# PowerClocks.net
KiCad netlist of a schematic drawn in Altium Designer
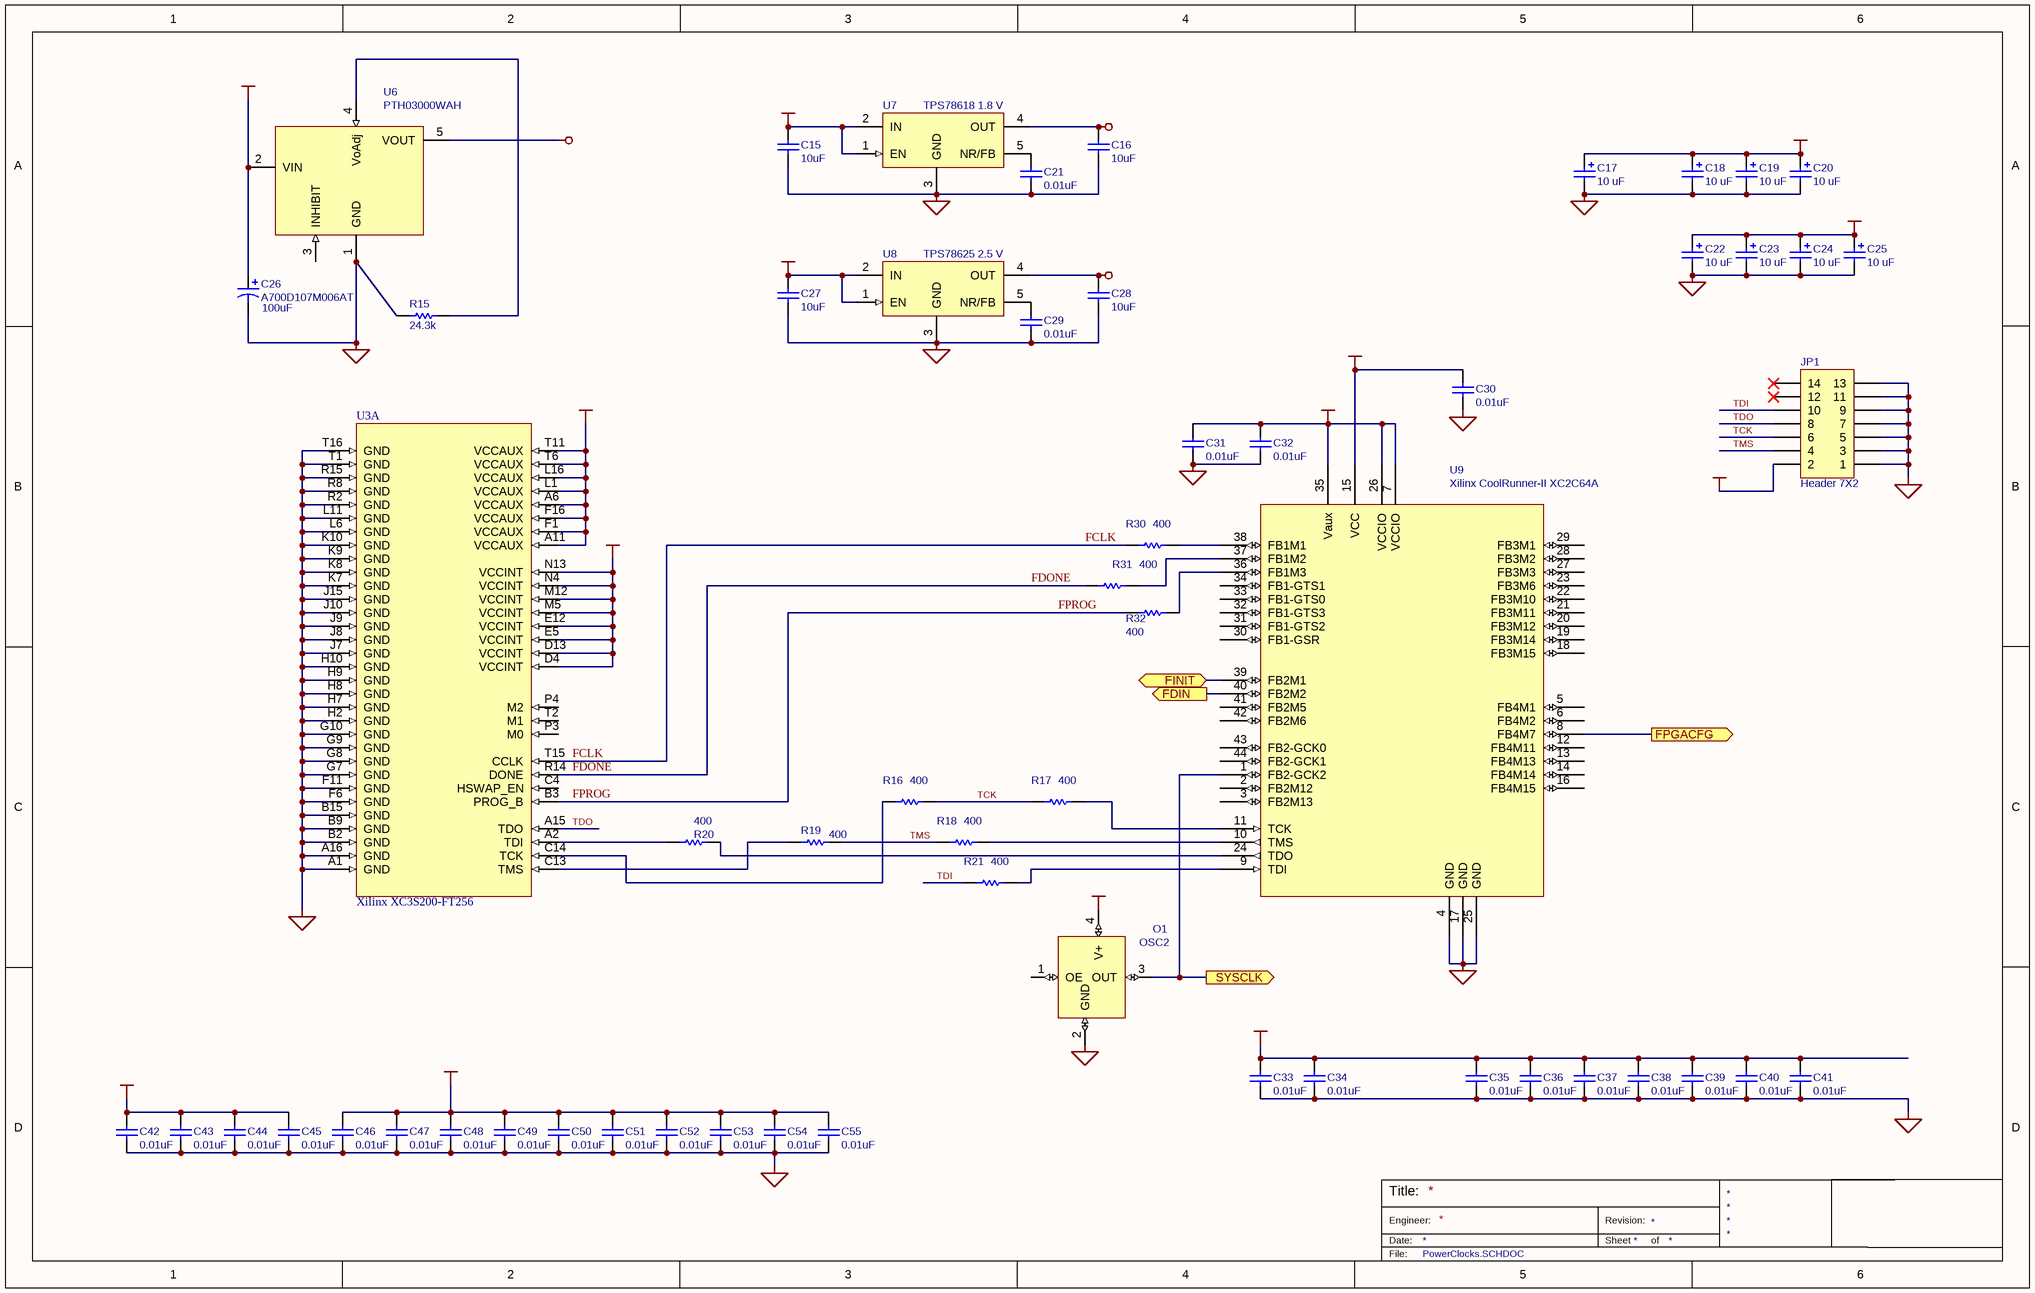
[diagram p0: PowerClocks.SCHDOC]

(export (version "E")
  (design (tool "Eeschema 10.0.6"))
  (components
    (comp (ref "C15")
      (value "10uF")
      (footprint "CC3216-1206")
      (description "Capacitor")
      (fields (field (name "PUBLISHER") "Altium Limited"))
      (libsource (lib "Miscellaneous Devices") (part "Cap"))
    )
    (comp (ref "C16")
      (value "10uF")
      (footprint "CC3216-1206")
      (description "Capacitor")
      (fields (field (name "PUBLISHER") "Altium Limited"))
      (libsource (lib "Miscellaneous Devices") (part "Cap"))
    )
    (comp (ref "C17")
      (value "10 uF")
      (footprint "TC3528-1411")
      (description "Tantalum Bypass cap")
      (fields
        (field (name "MANUFACTURER") "Generic Components")
        (field (name "Comment") "Bypass Cap")
        (field (name "PUBLISHER") "Altium Limited")
      )
      (libsource (lib "Miscellaneous Devices") (part "Cap Pol3"))
    )
    (comp (ref "C18")
      (value "10 uF")
      (footprint "TC3528-1411")
      (description "Tantalum Bypass cap")
      (fields
        (field (name "MANUFACTURER") "Generic Components")
        (field (name "Comment") "Bypass Cap")
        (field (name "PUBLISHER") "Altium Limited")
      )
      (libsource (lib "Miscellaneous Devices") (part "Cap Pol3"))
    )
    (comp (ref "C19")
      (value "10 uF")
      (footprint "TC3528-1411")
      (description "Tantalum Bypass cap")
      (fields
        (field (name "MANUFACTURER") "Generic Components")
        (field (name "Comment") "Bypass Cap")
        (field (name "PUBLISHER") "Altium Limited")
      )
      (libsource (lib "Miscellaneous Devices") (part "Cap Pol3"))
    )
    (comp (ref "C20")
      (value "10 uF")
      (footprint "TC3528-1411")
      (description "Tantalum Bypass cap")
      (fields
        (field (name "MANUFACTURER") "Generic Components")
        (field (name "Comment") "Bypass Cap")
        (field (name "PUBLISHER") "Altium Limited")
      )
      (libsource (lib "Miscellaneous Devices") (part "Cap Pol3"))
    )
    (comp (ref "C21")
      (value "0.01uF")
      (footprint "CC1005-0402")
      (description "Capacitor")
      (fields (field (name "Comment") "Cap") (field (name "PUBLISHER") "Altium Limited"))
      (libsource (lib "Miscellaneous Devices") (part "Cap"))
    )
    (comp (ref "C22")
      (value "10 uF")
      (footprint "TC3528-1411")
      (description "Tantalum Bypass cap")
      (fields
        (field (name "MANUFACTURER") "Generic Components")
        (field (name "Comment") "Bypass Cap")
        (field (name "PUBLISHER") "Altium Limited")
      )
      (libsource (lib "Miscellaneous Devices") (part "Cap Pol3"))
    )
    (comp (ref "C23")
      (value "10 uF")
      (footprint "TC3528-1411")
      (description "Tantalum Bypass cap")
      (fields
        (field (name "MANUFACTURER") "Generic Components")
        (field (name "Comment") "Bypass Cap")
        (field (name "PUBLISHER") "Altium Limited")
      )
      (libsource (lib "Miscellaneous Devices") (part "Cap Pol3"))
    )
    (comp (ref "C24")
      (value "10 uF")
      (footprint "TC3528-1411")
      (description "Tantalum Bypass cap")
      (fields
        (field (name "MANUFACTURER") "Generic Components")
        (field (name "Comment") "Bypass Cap")
        (field (name "PUBLISHER") "Altium Limited")
      )
      (libsource (lib "Miscellaneous Devices") (part "Cap Pol3"))
    )
    (comp (ref "C25")
      (value "10 uF")
      (footprint "TC3528-1411")
      (description "Tantalum Bypass cap")
      (fields
        (field (name "MANUFACTURER") "Generic Components")
        (field (name "Comment") "Bypass Cap")
        (field (name "PUBLISHER") "Altium Limited")
      )
      (libsource (lib "Miscellaneous Devices") (part "Cap Pol3"))
    )
    (comp (ref "C26")
      (value "A700D107M006AT")
      (footprint "TC7343-2917")
      (description "Polarized Capacitor (Radial)")
      (fields (field (name "ALTIUM_VALUE") "100uF") (field (name "PUBLISHER") "Altium Limited"))
      (libsource (lib "Miscellaneous Devices") (part "Cap Pol1"))
    )
    (comp (ref "C27")
      (value "10uF")
      (footprint "CC3216-1206")
      (description "Capacitor")
      (fields (field (name "PUBLISHER") "Altium Limited"))
      (libsource (lib "Miscellaneous Devices") (part "Cap"))
    )
    (comp (ref "C28")
      (value "10uF")
      (footprint "CC3216-1206")
      (description "Capacitor")
      (fields (field (name "PUBLISHER") "Altium Limited"))
      (libsource (lib "Miscellaneous Devices") (part "Cap"))
    )
    (comp (ref "C29")
      (value "0.01uF")
      (footprint "CC1005-0402")
      (description "Capacitor")
      (fields (field (name "Comment") "Cap") (field (name "PUBLISHER") "Altium Limited"))
      (libsource (lib "Miscellaneous Devices") (part "Cap"))
    )
    (comp (ref "C30")
      (value "0.01uF")
      (footprint "CC1005-0402")
      (description "Capacitor")
      (fields
        (field (name "MANUFACTURER") "Generic Components")
        (field (name "Comment") "Cap")
        (field (name "PUBLISHER") "Altium Limited")
      )
      (libsource (lib "Miscellaneous Devices") (part "Cap"))
    )
    (comp (ref "C31")
      (value "0.01uF")
      (footprint "CC1005-0402")
      (description "Capacitor")
      (fields
        (field (name "MANUFACTURER") "Generic Components")
        (field (name "Comment") "Cap")
        (field (name "PUBLISHER") "Altium Limited")
      )
      (libsource (lib "Miscellaneous Devices") (part "Cap"))
    )
    (comp (ref "C32")
      (value "0.01uF")
      (footprint "CC1005-0402")
      (description "Capacitor")
      (fields
        (field (name "MANUFACTURER") "Generic Components")
        (field (name "Comment") "Cap")
        (field (name "PUBLISHER") "Altium Limited")
      )
      (libsource (lib "Miscellaneous Devices") (part "Cap"))
    )
    (comp (ref "C33")
      (value "0.01uF")
      (footprint "CC1005-0402")
      (description "Capacitor")
      (fields
        (field (name "MANUFACTURER") "Generic Components")
        (field (name "Comment") "Cap")
        (field (name "PUBLISHER") "Altium Limited")
      )
      (libsource (lib "Miscellaneous Devices") (part "Cap"))
    )
    (comp (ref "C34")
      (value "0.01uF")
      (footprint "CC1005-0402")
      (description "Capacitor")
      (fields
        (field (name "MANUFACTURER") "Generic Components")
        (field (name "Comment") "Cap")
        (field (name "PUBLISHER") "Altium Limited")
      )
      (libsource (lib "Miscellaneous Devices") (part "Cap"))
    )
    (comp (ref "C35")
      (value "0.01uF")
      (footprint "CC1005-0402")
      (description "Capacitor")
      (fields
        (field (name "MANUFACTURER") "Generic Components")
        (field (name "Comment") "Cap")
        (field (name "PUBLISHER") "Altium Limited")
      )
      (libsource (lib "Miscellaneous Devices") (part "Cap"))
    )
    (comp (ref "C36")
      (value "0.01uF")
      (footprint "CC1005-0402")
      (description "Capacitor")
      (fields
        (field (name "MANUFACTURER") "Generic Components")
        (field (name "Comment") "Cap")
        (field (name "PUBLISHER") "Altium Limited")
      )
      (libsource (lib "Miscellaneous Devices") (part "Cap"))
    )
    (comp (ref "C37")
      (value "0.01uF")
      (footprint "CC1005-0402")
      (description "Capacitor")
      (fields
        (field (name "MANUFACTURER") "Generic Components")
        (field (name "Comment") "Cap")
        (field (name "PUBLISHER") "Altium Limited")
      )
      (libsource (lib "Miscellaneous Devices") (part "Cap"))
    )
    (comp (ref "C38")
      (value "0.01uF")
      (footprint "CC1005-0402")
      (description "Capacitor")
      (fields
        (field (name "MANUFACTURER") "Generic Components")
        (field (name "Comment") "Cap")
        (field (name "PUBLISHER") "Altium Limited")
      )
      (libsource (lib "Miscellaneous Devices") (part "Cap"))
    )
    (comp (ref "C39")
      (value "0.01uF")
      (footprint "CC1005-0402")
      (description "Capacitor")
      (fields
        (field (name "MANUFACTURER") "Generic Components")
        (field (name "Comment") "Cap")
        (field (name "PUBLISHER") "Altium Limited")
      )
      (libsource (lib "Miscellaneous Devices") (part "Cap"))
    )
    (comp (ref "C40")
      (value "0.01uF")
      (footprint "CC1005-0402")
      (description "Capacitor")
      (fields
        (field (name "MANUFACTURER") "Generic Components")
        (field (name "Comment") "Cap")
        (field (name "PUBLISHER") "Altium Limited")
      )
      (libsource (lib "Miscellaneous Devices") (part "Cap"))
    )
    (comp (ref "C41")
      (value "0.01uF")
      (footprint "CC1005-0402")
      (description "Capacitor")
      (fields
        (field (name "MANUFACTURER") "Generic Components")
        (field (name "Comment") "Cap")
        (field (name "PUBLISHER") "Altium Limited")
      )
      (libsource (lib "Miscellaneous Devices") (part "Cap"))
    )
    (comp (ref "C42")
      (value "0.01uF")
      (footprint "CC1005-0402")
      (description "Capacitor")
      (fields
        (field (name "MANUFACTURER") "Generic Components")
        (field (name "Comment") "Cap")
        (field (name "PUBLISHER") "Altium Limited")
      )
      (libsource (lib "Miscellaneous Devices") (part "Cap"))
    )
    (comp (ref "C43")
      (value "0.01uF")
      (footprint "CC1005-0402")
      (description "Capacitor")
      (fields
        (field (name "MANUFACTURER") "Generic Components")
        (field (name "Comment") "Cap")
        (field (name "PUBLISHER") "Altium Limited")
      )
      (libsource (lib "Miscellaneous Devices") (part "Cap"))
    )
    (comp (ref "C44")
      (value "0.01uF")
      (footprint "CC1005-0402")
      (description "Capacitor")
      (fields
        (field (name "MANUFACTURER") "Generic Components")
        (field (name "Comment") "Cap")
        (field (name "PUBLISHER") "Altium Limited")
      )
      (libsource (lib "Miscellaneous Devices") (part "Cap"))
    )
    (comp (ref "C45")
      (value "0.01uF")
      (footprint "CC1005-0402")
      (description "Capacitor")
      (fields
        (field (name "MANUFACTURER") "Generic Components")
        (field (name "Comment") "Cap")
        (field (name "PUBLISHER") "Altium Limited")
      )
      (libsource (lib "Miscellaneous Devices") (part "Cap"))
    )
    (comp (ref "C46")
      (value "0.01uF")
      (footprint "CC1005-0402")
      (description "Capacitor")
      (fields
        (field (name "MANUFACTURER") "Generic Components")
        (field (name "Comment") "Cap")
        (field (name "PUBLISHER") "Altium Limited")
      )
      (libsource (lib "Miscellaneous Devices") (part "Cap"))
    )
    (comp (ref "C47")
      (value "0.01uF")
      (footprint "CC1005-0402")
      (description "Capacitor")
      (fields
        (field (name "MANUFACTURER") "Generic Components")
        (field (name "Comment") "Cap")
        (field (name "PUBLISHER") "Altium Limited")
      )
      (libsource (lib "Miscellaneous Devices") (part "Cap"))
    )
    (comp (ref "C48")
      (value "0.01uF")
      (footprint "CC1005-0402")
      (description "Capacitor")
      (fields
        (field (name "MANUFACTURER") "Generic Components")
        (field (name "Comment") "Cap")
        (field (name "PUBLISHER") "Altium Limited")
      )
      (libsource (lib "Miscellaneous Devices") (part "Cap"))
    )
    (comp (ref "C49")
      (value "0.01uF")
      (footprint "CC1005-0402")
      (description "Capacitor")
      (fields
        (field (name "MANUFACTURER") "Generic Components")
        (field (name "Comment") "Cap")
        (field (name "PUBLISHER") "Altium Limited")
      )
      (libsource (lib "Miscellaneous Devices") (part "Cap"))
    )
    (comp (ref "C50")
      (value "0.01uF")
      (footprint "CC1005-0402")
      (description "Capacitor")
      (fields
        (field (name "MANUFACTURER") "Generic Components")
        (field (name "Comment") "Cap")
        (field (name "PUBLISHER") "Altium Limited")
      )
      (libsource (lib "Miscellaneous Devices") (part "Cap"))
    )
    (comp (ref "C51")
      (value "0.01uF")
      (footprint "CC1005-0402")
      (description "Capacitor")
      (fields
        (field (name "MANUFACTURER") "Generic Components")
        (field (name "Comment") "Cap")
        (field (name "PUBLISHER") "Altium Limited")
      )
      (libsource (lib "Miscellaneous Devices") (part "Cap"))
    )
    (comp (ref "C52")
      (value "0.01uF")
      (footprint "CC1005-0402")
      (description "Capacitor")
      (fields
        (field (name "MANUFACTURER") "Generic Components")
        (field (name "Comment") "Cap")
        (field (name "PUBLISHER") "Altium Limited")
      )
      (libsource (lib "Miscellaneous Devices") (part "Cap"))
    )
    (comp (ref "C53")
      (value "0.01uF")
      (footprint "CC1005-0402")
      (description "Capacitor")
      (fields
        (field (name "MANUFACTURER") "Generic Components")
        (field (name "Comment") "Cap")
        (field (name "PUBLISHER") "Altium Limited")
      )
      (libsource (lib "Miscellaneous Devices") (part "Cap"))
    )
    (comp (ref "C54")
      (value "0.01uF")
      (footprint "CC1005-0402")
      (description "Capacitor")
      (fields
        (field (name "MANUFACTURER") "Generic Components")
        (field (name "Comment") "Cap")
        (field (name "PUBLISHER") "Altium Limited")
      )
      (libsource (lib "Miscellaneous Devices") (part "Cap"))
    )
    (comp (ref "C55")
      (value "0.01uF")
      (footprint "CC1005-0402")
      (description "Capacitor")
      (fields
        (field (name "MANUFACTURER") "Generic Components")
        (field (name "Comment") "Cap")
        (field (name "PUBLISHER") "Altium Limited")
      )
      (libsource (lib "Miscellaneous Devices") (part "Cap"))
    )
    (comp (ref "JP1")
      (value "Header 7X2")
      (footprint "HDR2x7-2mm")
      (description "Header, 7-Pin, Dual row")
      (fields (field (name "MANUFACTURER") "Generic Components") (field (name "PUBLISHER") "Altium Limited"))
      (libsource (lib "Miscellaneous Connectors") (part "Header 7X2"))
    )
    (comp (ref "O1")
      (value "OSC2")
      (footprint "ECS-3953M")
      (description "ECS SMD Oscillator, ECS-3953M")
      (libsource (lib "parts") (part "OSC2"))
    )
    (comp (ref "R15")
      (value "24.3k")
      (footprint "CR3216-1206")
      (description "Resistor")
      (fields (field (name "Comment") "Res1") (field (name "PUBLISHER") "Altium Limited"))
      (libsource (lib "Miscellaneous Devices") (part "Res1"))
    )
    (comp (ref "R16")
      (value "400")
      (footprint "CR1608-0603")
      (description "Resistor")
      (fields
        (field (name "MANUFACTURER") "Generic Components")
        (field (name "Comment") "current-limiting series res")
        (field (name "PUBLISHER") "Altium Limited")
      )
      (libsource (lib "Miscellaneous Devices") (part "Res1"))
    )
    (comp (ref "R17")
      (value "400")
      (footprint "CR1608-0603")
      (description "Resistor")
      (fields
        (field (name "MANUFACTURER") "Generic Components")
        (field (name "Comment") "current-limiting series res")
        (field (name "PUBLISHER") "Altium Limited")
      )
      (libsource (lib "Miscellaneous Devices") (part "Res1"))
    )
    (comp (ref "R18")
      (value "400")
      (footprint "CR1608-0603")
      (description "Resistor")
      (fields
        (field (name "MANUFACTURER") "Generic Components")
        (field (name "Comment") "current-limiting series res")
        (field (name "PUBLISHER") "Altium Limited")
      )
      (libsource (lib "Miscellaneous Devices") (part "Res1"))
    )
    (comp (ref "R19")
      (value "400")
      (footprint "CR1608-0603")
      (description "Resistor")
      (fields
        (field (name "MANUFACTURER") "Generic Components")
        (field (name "Comment") "current-limiting series res")
        (field (name "PUBLISHER") "Altium Limited")
      )
      (libsource (lib "Miscellaneous Devices") (part "Res1"))
    )
    (comp (ref "R20")
      (value "400")
      (footprint "CR1608-0603")
      (description "Resistor")
      (fields
        (field (name "MANUFACTURER") "Generic Components")
        (field (name "Comment") "current-limiting series res")
        (field (name "PUBLISHER") "Altium Limited")
      )
      (libsource (lib "Miscellaneous Devices") (part "Res1"))
    )
    (comp (ref "R21")
      (value "400")
      (footprint "CR1608-0603")
      (description "Resistor")
      (fields
        (field (name "MANUFACTURER") "Generic Components")
        (field (name "Comment") "current-limiting series res")
        (field (name "PUBLISHER") "Altium Limited")
      )
      (libsource (lib "Miscellaneous Devices") (part "Res1"))
    )
    (comp (ref "R30")
      (value "400")
      (footprint "CR1608-0603")
      (description "Resistor")
      (fields
        (field (name "MANUFACTURER") "Generic Components")
        (field (name "Comment") "current-limiting series res")
        (field (name "PUBLISHER") "Altium Limited")
      )
      (libsource (lib "Miscellaneous Devices") (part "Res1"))
    )
    (comp (ref "R31")
      (value "400")
      (footprint "CR1608-0603")
      (description "Resistor")
      (fields
        (field (name "MANUFACTURER") "Generic Components")
        (field (name "Comment") "current-limiting series res")
        (field (name "PUBLISHER") "Altium Limited")
      )
      (libsource (lib "Miscellaneous Devices") (part "Res1"))
    )
    (comp (ref "R32")
      (value "400")
      (footprint "CR1608-0603")
      (description "Resistor")
      (fields
        (field (name "MANUFACTURER") "Generic Components")
        (field (name "Comment") "current-limiting series res")
        (field (name "PUBLISHER") "Altium Limited")
      )
      (libsource (lib "Miscellaneous Devices") (part "Res1"))
    )
    (comp (ref "U3")
      (value "Xilinx XC3S200-FT256")
      (footprint "Xilinx FT256 BGA")
      (description "Xilinx Spartan-3 FPGA")
      (libsource (lib "parts") (part "XC3S200-FT256"))
    )
    (comp (ref "U6") (value "PTH03000WAH") (footprint "TI EUS") (libsource (lib "parts") (part "PTH03000")))
    (comp (ref "U7")
      (value "TPS78618 1.8 V")
      (footprint "KTT")
      (description "TI 1.5A LDO")
      (libsource (lib "parts") (part "TPS786XX"))
    )
    (comp (ref "U8")
      (value "TPS78625 2.5 V")
      (footprint "KTT")
      (description "TI 1.5A LDO")
      (libsource (lib "parts") (part "TPS786XX"))
    )
    (comp (ref "U9")
      (value "Xilinx CoolRunner-II XC2C64A")
      (footprint "QFP10x10-G44/G10N")
      (libsource (lib "parts") (part "XC2C64A-5VQ44C"))
    )
  )
  (nets
    (net (code "1") (name "+1.2VCC") (class "Default")
      (node (ref "C22") (pin "1") (pinfunction "1_1") (pintype "passive"))
      (node (ref "C23") (pin "1") (pinfunction "1_1") (pintype "passive"))
      (node (ref "C24") (pin "1") (pinfunction "1_1") (pintype "passive"))
      (node (ref "C25") (pin "1") (pinfunction "1_1") (pintype "passive"))
      (node (ref "C42") (pin "2") (pinfunction "2_2") (pintype "passive"))
      (node (ref "C43") (pin "2") (pinfunction "2_2") (pintype "passive"))
      (node (ref "C44") (pin "2") (pinfunction "2_2") (pintype "passive"))
      (node (ref "C45") (pin "2") (pinfunction "2_2") (pintype "passive"))
      (node (ref "U3") (pin "D13") (pinfunction "VCCINT_D13") (pintype "input"))
      (node (ref "U3") (pin "D4") (pinfunction "VCCINT_D4") (pintype "input"))
      (node (ref "U3") (pin "E12") (pinfunction "VCCINT_E12") (pintype "input"))
      (node (ref "U3") (pin "E5") (pinfunction "VCCINT_E5") (pintype "input"))
      (node (ref "U3") (pin "M12") (pinfunction "VCCINT_M12") (pintype "input"))
      (node (ref "U3") (pin "M5") (pinfunction "VCCINT_M5") (pintype "input"))
      (node (ref "U3") (pin "N13") (pinfunction "VCCINT_N13") (pintype "input"))
      (node (ref "U3") (pin "N4") (pinfunction "VCCINT_N4") (pintype "input"))
      (node (ref "U6") (pin "5") (pinfunction "VOUT_5") (pintype "power_in"))
    )
    (net (code "2") (name "+1.8VCC") (class "Default")
      (node (ref "C16") (pin "2") (pinfunction "2_2") (pintype "passive"))
      (node (ref "C30") (pin "2") (pinfunction "2_2") (pintype "passive"))
      (node (ref "U7") (pin "4") (pinfunction "OUT_4") (pintype "power_in"))
      (node (ref "U9") (pin "15") (pinfunction "VCC_15") (pintype "power_in"))
    )
    (net (code "3") (name "+2.5VCC") (class "Default")
      (node (ref "C28") (pin "2") (pinfunction "2_2") (pintype "passive"))
      (node (ref "C46") (pin "2") (pinfunction "2_2") (pintype "passive"))
      (node (ref "C47") (pin "2") (pinfunction "2_2") (pintype "passive"))
      (node (ref "C48") (pin "2") (pinfunction "2_2") (pintype "passive"))
      (node (ref "C49") (pin "2") (pinfunction "2_2") (pintype "passive"))
      (node (ref "C50") (pin "2") (pinfunction "2_2") (pintype "passive"))
      (node (ref "C51") (pin "2") (pinfunction "2_2") (pintype "passive"))
      (node (ref "C52") (pin "2") (pinfunction "2_2") (pintype "passive"))
      (node (ref "C53") (pin "2") (pinfunction "2_2") (pintype "passive"))
      (node (ref "C54") (pin "2") (pinfunction "2_2") (pintype "passive"))
      (node (ref "C55") (pin "2") (pinfunction "2_2") (pintype "passive"))
      (node (ref "U3") (pin "A11") (pinfunction "VCCAUX_A11") (pintype "input"))
      (node (ref "U3") (pin "A6") (pinfunction "VCCAUX_A6") (pintype "input"))
      (node (ref "U3") (pin "F1") (pinfunction "VCCAUX_F1") (pintype "input"))
      (node (ref "U3") (pin "F16") (pinfunction "VCCAUX_F16") (pintype "input"))
      (node (ref "U3") (pin "L1") (pinfunction "VCCAUX_L1") (pintype "input"))
      (node (ref "U3") (pin "L16") (pinfunction "VCCAUX_L16") (pintype "input"))
      (node (ref "U3") (pin "T11") (pinfunction "VCCAUX_T11") (pintype "input"))
      (node (ref "U3") (pin "T6") (pinfunction "VCCAUX_T6") (pintype "input"))
      (node (ref "U8") (pin "4") (pinfunction "OUT_4") (pintype "power_in"))
    )
    (net (code "4") (name "/FCLK") (class "Default")
      (node (ref "R30") (pin "2") (pinfunction "2_2") (pintype "passive"))
      (node (ref "U3") (pin "T15") (pinfunction "CCLK_T15") (pintype "input"))
    )
    (net (code "5") (name "/FDIN") (class "Default")
      (node (ref "U9") (pin "40") (pinfunction "FB2M2_40") (pintype "bidirectional"))
    )
    (net (code "6") (name "/FDONE") (class "Default")
      (node (ref "R31") (pin "2") (pinfunction "2_2") (pintype "passive"))
      (node (ref "U3") (pin "R14") (pinfunction "DONE_R14") (pintype "input"))
    )
    (net (code "7") (name "/FINIT") (class "Default")
      (node (ref "U9") (pin "39") (pinfunction "FB2M1_39") (pintype "bidirectional"))
    )
    (net (code "8") (name "/FPGACFG") (class "Default")
      (node (ref "U9") (pin "8") (pinfunction "FB4M7_8") (pintype "bidirectional"))
    )
    (net (code "9") (name "/FPROG") (class "Default")
      (node (ref "R32") (pin "2") (pinfunction "2_2") (pintype "passive"))
      (node (ref "U3") (pin "B3") (pinfunction "PROG_B_B3") (pintype "input"))
    )
    (net (code "10") (name "/SYSCLK") (class "Default")
      (node (ref "O1") (pin "3") (pinfunction "OUT_3") (pintype "bidirectional"))
      (node (ref "U9") (pin "1") (pinfunction "FB2-GCK2_1") (pintype "bidirectional"))
    )
    (net (code "11") (name "/TCK") (class "Default")
      (node (ref "JP1") (pin "6") (pinfunction "6_6") (pintype "passive"))
      (node (ref "R16") (pin "1") (pinfunction "1_1") (pintype "passive"))
      (node (ref "R17") (pin "2") (pinfunction "2_2") (pintype "passive"))
    )
    (net (code "12") (name "/TDI") (class "Default")
      (node (ref "JP1") (pin "10") (pinfunction "10_10") (pintype "passive"))
      (node (ref "R21") (pin "2") (pinfunction "2_2") (pintype "passive"))
    )
    (net (code "13") (name "/TDO") (class "Default")
      (node (ref "JP1") (pin "8") (pinfunction "8_8") (pintype "passive"))
      (node (ref "U3") (pin "A15") (pinfunction "TDO_A15") (pintype "input"))
    )
    (net (code "14") (name "/TMS") (class "Default")
      (node (ref "JP1") (pin "4") (pinfunction "4_4") (pintype "passive"))
      (node (ref "R18") (pin "2") (pinfunction "2_2") (pintype "passive"))
      (node (ref "R19") (pin "2") (pinfunction "2_2") (pintype "passive"))
    )
    (net (code "15") (name "GND") (class "Default")
      (node (ref "C15") (pin "1") (pinfunction "1_1") (pintype "passive"))
      (node (ref "C16") (pin "1") (pinfunction "1_1") (pintype "passive"))
      (node (ref "C17") (pin "2") (pinfunction "2_2") (pintype "passive"))
      (node (ref "C18") (pin "2") (pinfunction "2_2") (pintype "passive"))
      (node (ref "C19") (pin "2") (pinfunction "2_2") (pintype "passive"))
      (node (ref "C20") (pin "2") (pinfunction "2_2") (pintype "passive"))
      (node (ref "C21") (pin "2") (pinfunction "2_2") (pintype "passive"))
      (node (ref "C22") (pin "2") (pinfunction "2_2") (pintype "passive"))
      (node (ref "C23") (pin "2") (pinfunction "2_2") (pintype "passive"))
      (node (ref "C24") (pin "2") (pinfunction "2_2") (pintype "passive"))
      (node (ref "C25") (pin "2") (pinfunction "2_2") (pintype "passive"))
      (node (ref "C26") (pin "2") (pinfunction "2_2") (pintype "passive"))
      (node (ref "C27") (pin "1") (pinfunction "1_1") (pintype "passive"))
      (node (ref "C28") (pin "1") (pinfunction "1_1") (pintype "passive"))
      (node (ref "C29") (pin "2") (pinfunction "2_2") (pintype "passive"))
      (node (ref "C30") (pin "1") (pinfunction "1_1") (pintype "passive"))
      (node (ref "C31") (pin "1") (pinfunction "1_1") (pintype "passive"))
      (node (ref "C32") (pin "1") (pinfunction "1_1") (pintype "passive"))
      (node (ref "C33") (pin "1") (pinfunction "1_1") (pintype "passive"))
      (node (ref "C34") (pin "1") (pinfunction "1_1") (pintype "passive"))
      (node (ref "C35") (pin "1") (pinfunction "1_1") (pintype "passive"))
      (node (ref "C36") (pin "1") (pinfunction "1_1") (pintype "passive"))
      (node (ref "C37") (pin "1") (pinfunction "1_1") (pintype "passive"))
      (node (ref "C38") (pin "1") (pinfunction "1_1") (pintype "passive"))
      (node (ref "C39") (pin "1") (pinfunction "1_1") (pintype "passive"))
      (node (ref "C40") (pin "1") (pinfunction "1_1") (pintype "passive"))
      (node (ref "C41") (pin "1") (pinfunction "1_1") (pintype "passive"))
      (node (ref "C42") (pin "1") (pinfunction "1_1") (pintype "passive"))
      (node (ref "C43") (pin "1") (pinfunction "1_1") (pintype "passive"))
      (node (ref "C44") (pin "1") (pinfunction "1_1") (pintype "passive"))
      (node (ref "C45") (pin "1") (pinfunction "1_1") (pintype "passive"))
      (node (ref "C46") (pin "1") (pinfunction "1_1") (pintype "passive"))
      (node (ref "C47") (pin "1") (pinfunction "1_1") (pintype "passive"))
      (node (ref "C48") (pin "1") (pinfunction "1_1") (pintype "passive"))
      (node (ref "C49") (pin "1") (pinfunction "1_1") (pintype "passive"))
      (node (ref "C50") (pin "1") (pinfunction "1_1") (pintype "passive"))
      (node (ref "C51") (pin "1") (pinfunction "1_1") (pintype "passive"))
      (node (ref "C52") (pin "1") (pinfunction "1_1") (pintype "passive"))
      (node (ref "C53") (pin "1") (pinfunction "1_1") (pintype "passive"))
      (node (ref "C54") (pin "1") (pinfunction "1_1") (pintype "passive"))
      (node (ref "C55") (pin "1") (pinfunction "1_1") (pintype "passive"))
      (node (ref "JP1") (pin "1") (pinfunction "1_1") (pintype "passive"))
      (node (ref "JP1") (pin "11") (pinfunction "11_11") (pintype "passive"))
      (node (ref "JP1") (pin "13") (pinfunction "13_13") (pintype "passive"))
      (node (ref "JP1") (pin "3") (pinfunction "3_3") (pintype "passive"))
      (node (ref "JP1") (pin "5") (pinfunction "5_5") (pintype "passive"))
      (node (ref "JP1") (pin "7") (pinfunction "7_7") (pintype "passive"))
      (node (ref "JP1") (pin "9") (pinfunction "9_9") (pintype "passive"))
      (node (ref "O1") (pin "2") (pinfunction "GND_2") (pintype "bidirectional"))
      (node (ref "R15") (pin "2") (pinfunction "2_2") (pintype "passive"))
      (node (ref "U3") (pin "A1") (pinfunction "GND_A1") (pintype "input"))
      (node (ref "U3") (pin "A16") (pinfunction "GND_A16") (pintype "input"))
      (node (ref "U3") (pin "B15") (pinfunction "GND_B15") (pintype "input"))
      (node (ref "U3") (pin "B2") (pinfunction "GND_B2") (pintype "input"))
      (node (ref "U3") (pin "B9") (pinfunction "GND_B9") (pintype "input"))
      (node (ref "U3") (pin "F11") (pinfunction "GND_F11") (pintype "input"))
      (node (ref "U3") (pin "F6") (pinfunction "GND_F6") (pintype "input"))
      (node (ref "U3") (pin "G10") (pinfunction "GND_G10") (pintype "input"))
      (node (ref "U3") (pin "G7") (pinfunction "GND_G7") (pintype "input"))
      (node (ref "U3") (pin "G8") (pinfunction "GND_G8") (pintype "input"))
      (node (ref "U3") (pin "G9") (pinfunction "GND_G9") (pintype "input"))
      (node (ref "U3") (pin "H10") (pinfunction "GND_H10") (pintype "input"))
      (node (ref "U3") (pin "H2") (pinfunction "GND_H2") (pintype "input"))
      (node (ref "U3") (pin "H7") (pinfunction "GND_H7") (pintype "input"))
      (node (ref "U3") (pin "H8") (pinfunction "GND_H8") (pintype "input"))
      (node (ref "U3") (pin "H9") (pinfunction "GND_H9") (pintype "input"))
      (node (ref "U3") (pin "J10") (pinfunction "GND_J10") (pintype "input"))
      (node (ref "U3") (pin "J15") (pinfunction "GND_J15") (pintype "input"))
      (node (ref "U3") (pin "J7") (pinfunction "GND_J7") (pintype "input"))
      (node (ref "U3") (pin "J8") (pinfunction "GND_J8") (pintype "input"))
      (node (ref "U3") (pin "J9") (pinfunction "GND_J9") (pintype "input"))
      (node (ref "U3") (pin "K10") (pinfunction "GND_K10") (pintype "input"))
      (node (ref "U3") (pin "K7") (pinfunction "GND_K7") (pintype "input"))
      (node (ref "U3") (pin "K8") (pinfunction "GND_K8") (pintype "input"))
      (node (ref "U3") (pin "K9") (pinfunction "GND_K9") (pintype "input"))
      (node (ref "U3") (pin "L11") (pinfunction "GND_L11") (pintype "input"))
      (node (ref "U3") (pin "L6") (pinfunction "GND_L6") (pintype "input"))
      (node (ref "U3") (pin "R15") (pinfunction "GND_R15") (pintype "input"))
      (node (ref "U3") (pin "R2") (pinfunction "GND_R2") (pintype "input"))
      (node (ref "U3") (pin "R8") (pinfunction "GND_R8") (pintype "input"))
      (node (ref "U3") (pin "T1") (pinfunction "GND_T1") (pintype "input"))
      (node (ref "U3") (pin "T16") (pinfunction "GND_T16") (pintype "input"))
      (node (ref "U6") (pin "1") (pinfunction "GND_1") (pintype "power_in"))
      (node (ref "U7") (pin "3") (pinfunction "GND_3") (pintype "power_in"))
      (node (ref "U8") (pin "3") (pinfunction "GND_3") (pintype "power_in"))
      (node (ref "U9") (pin "17") (pinfunction "GND_17") (pintype "power_in"))
      (node (ref "U9") (pin "25") (pinfunction "GND_25") (pintype "power_in"))
      (node (ref "U9") (pin "4") (pinfunction "GND_4") (pintype "power_in"))
    )
    (net (code "16") (name "Net-(U3A-TCK)") (class "Default")
      (node (ref "R16") (pin "2") (pinfunction "2_2") (pintype "passive"))
      (node (ref "U3") (pin "C14") (pinfunction "TCK_C14") (pintype "input"))
    )
    (net (code "17") (name "Net-(U3A-TDI)") (class "Default")
      (node (ref "R20") (pin "2") (pinfunction "2_2") (pintype "passive"))
      (node (ref "U3") (pin "A2") (pinfunction "TDI_A2") (pintype "input"))
    )
    (net (code "18") (name "Net-(U3A-TMS)") (class "Default")
      (node (ref "R19") (pin "1") (pinfunction "1_1") (pintype "passive"))
      (node (ref "U3") (pin "C13") (pinfunction "TMS_C13") (pintype "input"))
    )
    (net (code "19") (name "Net-(U6-VoAdj)") (class "Default")
      (node (ref "R15") (pin "1") (pinfunction "1_1") (pintype "passive"))
      (node (ref "U6") (pin "4") (pinfunction "VoAdj_4") (pintype "input"))
    )
    (net (code "20") (name "Net-(U7-NR{slash}FB)") (class "Default")
      (node (ref "C21") (pin "1") (pinfunction "1_1") (pintype "passive"))
      (node (ref "U7") (pin "5") (pinfunction "NR/FB_5") (pintype "power_in"))
    )
    (net (code "21") (name "Net-(U8-NR{slash}FB)") (class "Default")
      (node (ref "C29") (pin "1") (pinfunction "1_1") (pintype "passive"))
      (node (ref "U8") (pin "5") (pinfunction "NR/FB_5") (pintype "power_in"))
    )
    (net (code "22") (name "Net-(U9-FB1M1)") (class "Default")
      (node (ref "R30") (pin "1") (pinfunction "1_1") (pintype "passive"))
      (node (ref "U9") (pin "38") (pinfunction "FB1M1_38") (pintype "bidirectional"))
    )
    (net (code "23") (name "Net-(U9-FB1M2)") (class "Default")
      (node (ref "R31") (pin "1") (pinfunction "1_1") (pintype "passive"))
      (node (ref "U9") (pin "37") (pinfunction "FB1M2_37") (pintype "bidirectional"))
    )
    (net (code "24") (name "Net-(U9-FB1M3)") (class "Default")
      (node (ref "R32") (pin "1") (pinfunction "1_1") (pintype "passive"))
      (node (ref "U9") (pin "36") (pinfunction "FB1M3_36") (pintype "bidirectional"))
    )
    (net (code "25") (name "Net-(U9-TCK)") (class "Default")
      (node (ref "R17") (pin "1") (pinfunction "1_1") (pintype "passive"))
      (node (ref "U9") (pin "11") (pinfunction "TCK_11") (pintype "input"))
    )
    (net (code "26") (name "Net-(U9-TDI)") (class "Default")
      (node (ref "R21") (pin "1") (pinfunction "1_1") (pintype "passive"))
      (node (ref "U9") (pin "9") (pinfunction "TDI_9") (pintype "input"))
    )
    (net (code "27") (name "Net-(U9-TDO)") (class "Default")
      (node (ref "R20") (pin "1") (pinfunction "1_1") (pintype "passive"))
      (node (ref "U9") (pin "24") (pinfunction "TDO_24") (pintype "output"))
    )
    (net (code "28") (name "Net-(U9-TMS)") (class "Default")
      (node (ref "R18") (pin "1") (pinfunction "1_1") (pintype "passive"))
      (node (ref "U9") (pin "10") (pinfunction "TMS_10") (pintype "output"))
    )
    (net (code "29") (name "VCC") (class "Default")
      (node (ref "C15") (pin "2") (pinfunction "2_2") (pintype "passive"))
      (node (ref "C17") (pin "1") (pinfunction "1_1") (pintype "passive"))
      (node (ref "C18") (pin "1") (pinfunction "1_1") (pintype "passive"))
      (node (ref "C19") (pin "1") (pinfunction "1_1") (pintype "passive"))
      (node (ref "C20") (pin "1") (pinfunction "1_1") (pintype "passive"))
      (node (ref "C26") (pin "1") (pinfunction "1_1") (pintype "passive"))
      (node (ref "C27") (pin "2") (pinfunction "2_2") (pintype "passive"))
      (node (ref "C31") (pin "2") (pinfunction "2_2") (pintype "passive"))
      (node (ref "C32") (pin "2") (pinfunction "2_2") (pintype "passive"))
      (node (ref "C33") (pin "2") (pinfunction "2_2") (pintype "passive"))
      (node (ref "C34") (pin "2") (pinfunction "2_2") (pintype "passive"))
      (node (ref "C35") (pin "2") (pinfunction "2_2") (pintype "passive"))
      (node (ref "C36") (pin "2") (pinfunction "2_2") (pintype "passive"))
      (node (ref "C37") (pin "2") (pinfunction "2_2") (pintype "passive"))
      (node (ref "C38") (pin "2") (pinfunction "2_2") (pintype "passive"))
      (node (ref "C39") (pin "2") (pinfunction "2_2") (pintype "passive"))
      (node (ref "C40") (pin "2") (pinfunction "2_2") (pintype "passive"))
      (node (ref "C41") (pin "2") (pinfunction "2_2") (pintype "passive"))
      (node (ref "JP1") (pin "2") (pinfunction "2_2") (pintype "passive"))
      (node (ref "O1") (pin "4") (pinfunction "V+_4") (pintype "bidirectional"))
      (node (ref "U6") (pin "2") (pinfunction "VIN_2") (pintype "power_in"))
      (node (ref "U7") (pin "1") (pinfunction "EN_1") (pintype "input"))
      (node (ref "U7") (pin "2") (pinfunction "IN_2") (pintype "power_in"))
      (node (ref "U8") (pin "1") (pinfunction "EN_1") (pintype "input"))
      (node (ref "U8") (pin "2") (pinfunction "IN_2") (pintype "power_in"))
      (node (ref "U9") (pin "26") (pinfunction "VCCIO_26") (pintype "power_in"))
      (node (ref "U9") (pin "35") (pinfunction "Vaux_35") (pintype "power_in"))
      (node (ref "U9") (pin "7") (pinfunction "VCCIO_7") (pintype "power_in"))
    )
    (net (code "30") (name "unconnected-(JP1-Pad12)") (class "Default")
      (node (ref "JP1") (pin "12") (pinfunction "12_12") (pintype "passive+no_connect"))
    )
    (net (code "31") (name "unconnected-(JP1-Pad14)") (class "Default")
      (node (ref "JP1") (pin "14") (pinfunction "14_14") (pintype "passive+no_connect"))
    )
    (net (code "32") (name "unconnected-(O1-OE-Pad1)") (class "Default")
      (node (ref "O1") (pin "1") (pinfunction "OE_1") (pintype "bidirectional"))
    )
    (net (code "33") (name "unconnected-(U3A-HSWAP_EN-PadC4)") (class "Default")
      (node (ref "U3") (pin "C4") (pinfunction "HSWAP_EN_C4") (pintype "input"))
    )
    (net (code "34") (name "unconnected-(U3A-M0-PadP3)") (class "Default")
      (node (ref "U3") (pin "P3") (pinfunction "M0_P3") (pintype "input"))
    )
    (net (code "35") (name "unconnected-(U3A-M1-PadT2)") (class "Default")
      (node (ref "U3") (pin "T2") (pinfunction "M1_T2") (pintype "input"))
    )
    (net (code "36") (name "unconnected-(U3A-M2-PadP4)") (class "Default")
      (node (ref "U3") (pin "P4") (pinfunction "M2_P4") (pintype "input"))
    )
    (net (code "37") (name "unconnected-(U6-INHIBIT-Pad3)") (class "Default")
      (node (ref "U6") (pin "3") (pinfunction "INHIBIT_3") (pintype "input"))
    )
    (net (code "38") (name "unconnected-(U9-FB1-GSR-Pad30)") (class "Default")
      (node (ref "U9") (pin "30") (pinfunction "FB1-GSR_30") (pintype "bidirectional"))
    )
    (net (code "39") (name "unconnected-(U9-FB1-GTS0-Pad33)") (class "Default")
      (node (ref "U9") (pin "33") (pinfunction "FB1-GTS0_33") (pintype "bidirectional"))
    )
    (net (code "40") (name "unconnected-(U9-FB1-GTS1-Pad34)") (class "Default")
      (node (ref "U9") (pin "34") (pinfunction "FB1-GTS1_34") (pintype "bidirectional"))
    )
    (net (code "41") (name "unconnected-(U9-FB1-GTS2-Pad31)") (class "Default")
      (node (ref "U9") (pin "31") (pinfunction "FB1-GTS2_31") (pintype "bidirectional"))
    )
    (net (code "42") (name "unconnected-(U9-FB1-GTS3-Pad32)") (class "Default")
      (node (ref "U9") (pin "32") (pinfunction "FB1-GTS3_32") (pintype "bidirectional"))
    )
    (net (code "43") (name "unconnected-(U9-FB2-GCK0-Pad43)") (class "Default")
      (node (ref "U9") (pin "43") (pinfunction "FB2-GCK0_43") (pintype "bidirectional"))
    )
    (net (code "44") (name "unconnected-(U9-FB2-GCK1-Pad44)") (class "Default")
      (node (ref "U9") (pin "44") (pinfunction "FB2-GCK1_44") (pintype "bidirectional"))
    )
    (net (code "45") (name "unconnected-(U9-FB2M5-Pad41)") (class "Default")
      (node (ref "U9") (pin "41") (pinfunction "FB2M5_41") (pintype "bidirectional"))
    )
    (net (code "46") (name "unconnected-(U9-FB2M6-Pad42)") (class "Default")
      (node (ref "U9") (pin "42") (pinfunction "FB2M6_42") (pintype "bidirectional"))
    )
    (net (code "47") (name "unconnected-(U9-FB2M12-Pad2)") (class "Default")
      (node (ref "U9") (pin "2") (pinfunction "FB2M12_2") (pintype "bidirectional"))
    )
    (net (code "48") (name "unconnected-(U9-FB2M13-Pad3)") (class "Default")
      (node (ref "U9") (pin "3") (pinfunction "FB2M13_3") (pintype "bidirectional"))
    )
    (net (code "49") (name "unconnected-(U9-FB3M1-Pad29)") (class "Default")
      (node (ref "U9") (pin "29") (pinfunction "FB3M1_29") (pintype "bidirectional"))
    )
    (net (code "50") (name "unconnected-(U9-FB3M2-Pad28)") (class "Default")
      (node (ref "U9") (pin "28") (pinfunction "FB3M2_28") (pintype "bidirectional"))
    )
    (net (code "51") (name "unconnected-(U9-FB3M3-Pad27)") (class "Default")
      (node (ref "U9") (pin "27") (pinfunction "FB3M3_27") (pintype "bidirectional"))
    )
    (net (code "52") (name "unconnected-(U9-FB3M6-Pad23)") (class "Default")
      (node (ref "U9") (pin "23") (pinfunction "FB3M6_23") (pintype "bidirectional"))
    )
    (net (code "53") (name "unconnected-(U9-FB3M10-Pad22)") (class "Default")
      (node (ref "U9") (pin "22") (pinfunction "FB3M10_22") (pintype "bidirectional"))
    )
    (net (code "54") (name "unconnected-(U9-FB3M11-Pad21)") (class "Default")
      (node (ref "U9") (pin "21") (pinfunction "FB3M11_21") (pintype "bidirectional"))
    )
    (net (code "55") (name "unconnected-(U9-FB3M12-Pad20)") (class "Default")
      (node (ref "U9") (pin "20") (pinfunction "FB3M12_20") (pintype "bidirectional"))
    )
    (net (code "56") (name "unconnected-(U9-FB3M14-Pad19)") (class "Default")
      (node (ref "U9") (pin "19") (pinfunction "FB3M14_19") (pintype "bidirectional"))
    )
    (net (code "57") (name "unconnected-(U9-FB3M15-Pad18)") (class "Default")
      (node (ref "U9") (pin "18") (pinfunction "FB3M15_18") (pintype "bidirectional"))
    )
    (net (code "58") (name "unconnected-(U9-FB4M1-Pad5)") (class "Default")
      (node (ref "U9") (pin "5") (pinfunction "FB4M1_5") (pintype "bidirectional"))
    )
    (net (code "59") (name "unconnected-(U9-FB4M2-Pad6)") (class "Default")
      (node (ref "U9") (pin "6") (pinfunction "FB4M2_6") (pintype "bidirectional"))
    )
    (net (code "60") (name "unconnected-(U9-FB4M11-Pad12)") (class "Default")
      (node (ref "U9") (pin "12") (pinfunction "FB4M11_12") (pintype "bidirectional"))
    )
    (net (code "61") (name "unconnected-(U9-FB4M13-Pad13)") (class "Default")
      (node (ref "U9") (pin "13") (pinfunction "FB4M13_13") (pintype "bidirectional"))
    )
    (net (code "62") (name "unconnected-(U9-FB4M14-Pad14)") (class "Default")
      (node (ref "U9") (pin "14") (pinfunction "FB4M14_14") (pintype "bidirectional"))
    )
    (net (code "63") (name "unconnected-(U9-FB4M15-Pad16)") (class "Default")
      (node (ref "U9") (pin "16") (pinfunction "FB4M15_16") (pintype "bidirectional"))
    )
  )
)
